# Valve.net
KiCad netlist of a schematic drawn in EAGLE
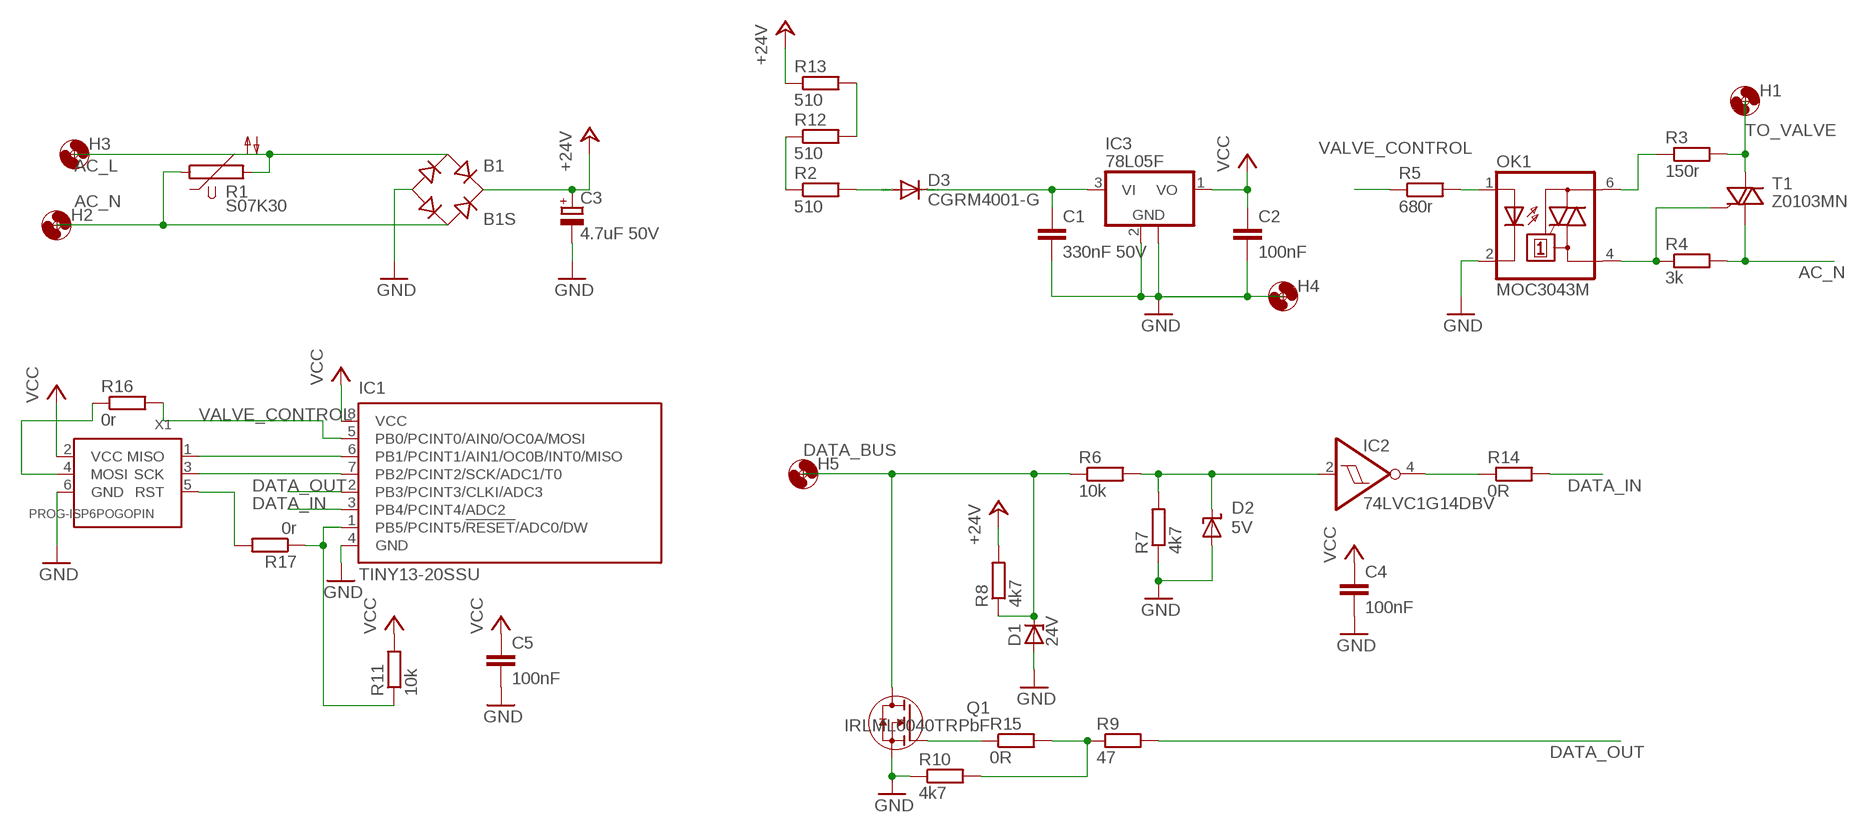
[diagram p0: schematic, sheet 1]

(export (version "E")
  (design (tool "Eeschema 10.0.6"))
  (components
    (comp (ref "B1")
      (value "B1S")
      (footprint "eagle-import:MBS")
      (libsource (lib "eagle-import") (part "BS1"))
    )
    (comp (ref "C1")
      (value "330nF 50V")
      (footprint "eagle-import:C0805K")
      (libsource (lib "eagle-import") (part "C-EUC0805K"))
    )
    (comp (ref "C2")
      (value "100nF")
      (footprint "eagle-import:C0805K")
      (libsource (lib "eagle-import") (part "C-EUC0805K"))
    )
    (comp (ref "C3")
      (value "4.7uF 50V")
      (footprint "eagle-import:D_7343-31R")
      (libsource (lib "eagle-import") (part "CPOL-EUD/7343-31R"))
    )
    (comp (ref "C4")
      (value "100nF")
      (footprint "eagle-import:0805")
      (libsource (lib "eagle-import") (part "C0805"))
    )
    (comp (ref "C5")
      (value "100nF")
      (footprint "eagle-import:C0805K")
      (libsource (lib "eagle-import") (part "C-EUC0805K"))
    )
    (comp (ref "D1")
      (value "24V")
      (footprint "eagle-import:SOT23")
      (libsource (lib "eagle-import") (part "ZENER-DIODESOT23"))
    )
    (comp (ref "D2")
      (value "5V")
      (footprint "eagle-import:SOD123")
      (libsource (lib "eagle-import") (part "ZENER"))
    )
    (comp (ref "D3")
      (value "CGRM4001-G")
      (footprint "eagle-import:SOD-123_MINI-SMA")
      (libsource (lib "eagle-import") (part "CGRM400-G1"))
    )
    (comp (ref "H1")
      (value "MOUNT-HOLE3.0")
      (footprint "eagle-import:3,0")
      (libsource (lib "eagle-import") (part "MOUNT-HOLE3.0"))
    )
    (comp (ref "H2")
      (value "MOUNT-HOLE3.0")
      (footprint "eagle-import:3,0")
      (libsource (lib "eagle-import") (part "MOUNT-HOLE3.0"))
    )
    (comp (ref "H3")
      (value "MOUNT-HOLE3.0")
      (footprint "eagle-import:3,0")
      (libsource (lib "eagle-import") (part "MOUNT-HOLE3.0"))
    )
    (comp (ref "H4")
      (value "MOUNT-HOLE3.0")
      (footprint "eagle-import:3,0")
      (libsource (lib "eagle-import") (part "MOUNT-HOLE3.0"))
    )
    (comp (ref "H5")
      (value "MOUNT-HOLE3.0")
      (footprint "eagle-import:3,0")
      (libsource (lib "eagle-import") (part "MOUNT-HOLE3.0"))
    )
    (comp (ref "IC1")
      (value "TINY13-20SSU")
      (footprint "eagle-import:8S1")
      (fields (field (name "MPN") "ATTINY13-20SSU"))
      (libsource (lib "eagle-import") (part "TINY13SSU-20"))
    )
    (comp (ref "IC2")
      (value "74LVC1G14DBV")
      (footprint "eagle-import:SOT23-5")
      (libsource (lib "eagle-import") (part "741G14DBVLVC"))
    )
    (comp (ref "IC3")
      (value "78L05F")
      (footprint "eagle-import:SOT89")
      (libsource (lib "eagle-import") (part "78LF05"))
    )
    (comp (ref "OK1")
      (value "MOC3043M")
      (footprint "eagle-import:DIL06")
      (fields (field (name "MF") "FAIRCHILD SEMICONDUCTOR") (field (name "MPN") "MOC3043-M"))
      (libsource (lib "eagle-import") (part "MOC3043M"))
    )
    (comp (ref "Q1")
      (value "IRLML0040TRPbF")
      (footprint "eagle-import:SOT-23-GSD")
      (libsource (lib "eagle-import") (part "SI2302"))
    )
    (comp (ref "R1")
      (value "S07K30")
      (footprint "eagle-import:S07K40")
      (libsource (lib "eagle-import") (part "S07K40"))
    )
    (comp (ref "R2")
      (value "510")
      (footprint "eagle-import:R2512")
      (libsource (lib "eagle-import") (part "R-EU_R2512"))
    )
    (comp (ref "R3")
      (value "150r")
      (footprint "eagle-import:R0805")
      (libsource (lib "eagle-import") (part "R-EU_R0805"))
    )
    (comp (ref "R4")
      (value "3k")
      (footprint "eagle-import:R0805")
      (libsource (lib "eagle-import") (part "R-EU_R0805"))
    )
    (comp (ref "R5")
      (value "680r")
      (footprint "eagle-import:R0805")
      (libsource (lib "eagle-import") (part "R-EU_R0805"))
    )
    (comp (ref "R6")
      (value "10k")
      (footprint "eagle-import:R0805")
      (libsource (lib "eagle-import") (part "R-EU_R0805"))
    )
    (comp (ref "R7")
      (value "4k7")
      (footprint "eagle-import:R0805")
      (libsource (lib "eagle-import") (part "R-EU_R0805"))
    )
    (comp (ref "R8")
      (value "4k7")
      (footprint "eagle-import:R0805")
      (libsource (lib "eagle-import") (part "R-EU_R0805"))
    )
    (comp (ref "R9")
      (value "47")
      (footprint "eagle-import:R0805")
      (libsource (lib "eagle-import") (part "R-EU_R0805"))
    )
    (comp (ref "R10")
      (value "4k7")
      (footprint "eagle-import:R0805")
      (libsource (lib "eagle-import") (part "R-EU_R0805"))
    )
    (comp (ref "R11")
      (value "10k")
      (footprint "eagle-import:R0805")
      (libsource (lib "eagle-import") (part "R-EU_R0805"))
    )
    (comp (ref "R12")
      (value "510")
      (footprint "eagle-import:R2512")
      (libsource (lib "eagle-import") (part "R-EU_R2512"))
    )
    (comp (ref "R13")
      (value "510")
      (footprint "eagle-import:R2512")
      (libsource (lib "eagle-import") (part "R-EU_R2512"))
    )
    (comp (ref "R14")
      (value "0R")
      (footprint "eagle-import:R1206W")
      (libsource (lib "eagle-import") (part "R-EU_R1206W"))
    )
    (comp (ref "R15")
      (value "0R")
      (footprint "eagle-import:R1206W")
      (libsource (lib "eagle-import") (part "R-EU_R1206W"))
    )
    (comp (ref "R16")
      (value "0r")
      (footprint "eagle-import:0805R")
      (libsource (lib "eagle-import") (part "R0805"))
    )
    (comp (ref "R17")
      (value "0r")
      (footprint "eagle-import:0805R")
      (libsource (lib "eagle-import") (part "R0805"))
    )
    (comp (ref "T1")
      (value "Z0103MN")
      (footprint "eagle-import:SOT223")
      (libsource (lib "eagle-import") (part "Z0103MN"))
    )
    (comp (ref "X1")
      (value "PROG-ISP6POGOPIN")
      (footprint "eagle-import:PROG_POGOPIN")
      (libsource (lib "eagle-import") (part "PROG-ISP6POGOPIN"))
    )
  )
  (nets
    (net (code "1") (name "+24V") (class "Default")
      (node (ref "B1") (pin "+") (pinfunction "+_+") (pintype "passive"))
      (node (ref "C3") (pin "+") (pinfunction "+_+") (pintype "passive"))
      (node (ref "R13") (pin "1") (pinfunction "1_1") (pintype "passive"))
      (node (ref "R8") (pin "2") (pinfunction "2_2") (pintype "passive"))
    )
    (net (code "2") (name "/AC_L") (class "Default")
      (node (ref "B1") (pin "AC1") (pinfunction "AC1_AC1") (pintype "passive"))
      (node (ref "H3") (pin "P$1") (pinfunction "P$1_P$1") (pintype "bidirectional"))
      (node (ref "R1") (pin "2") (pinfunction "2_2") (pintype "passive"))
    )
    (net (code "3") (name "/AC_N") (class "Default")
      (node (ref "B1") (pin "AC2") (pinfunction "AC2_AC2") (pintype "passive"))
      (node (ref "H2") (pin "P$1") (pinfunction "P$1_P$1") (pintype "bidirectional"))
      (node (ref "R1") (pin "1") (pinfunction "1_1") (pintype "passive"))
      (node (ref "R4") (pin "2") (pinfunction "2_2") (pintype "passive"))
      (node (ref "T1") (pin "1") (pinfunction "A1_1") (pintype "passive"))
    )
    (net (code "4") (name "/DATA_BUS") (class "Default")
      (node (ref "D1") (pin "3") (pinfunction "C_3") (pintype "passive"))
      (node (ref "H5") (pin "P$1") (pinfunction "P$1_P$1") (pintype "bidirectional"))
      (node (ref "Q1") (pin "D") (pinfunction "D_D") (pintype "passive"))
      (node (ref "R6") (pin "1") (pinfunction "1_1") (pintype "passive"))
      (node (ref "R8") (pin "1") (pinfunction "1_1") (pintype "passive"))
    )
    (net (code "5") (name "/DATA_IN") (class "Default")
      (node (ref "IC1") (pin "3") (pinfunction "PB4/PCINT4/ADC2_3") (pintype "bidirectional"))
      (node (ref "R14") (pin "2") (pinfunction "2_2") (pintype "passive"))
    )
    (net (code "6") (name "/DATA_OUT") (class "Default")
      (node (ref "IC1") (pin "2") (pinfunction "PB3/PCINT3/CLKI/ADC3_2") (pintype "bidirectional"))
      (node (ref "R9") (pin "2") (pinfunction "2_2") (pintype "passive"))
    )
    (net (code "7") (name "/TO_VALVE") (class "Default")
      (node (ref "H1") (pin "P$1") (pinfunction "P$1_P$1") (pintype "bidirectional"))
      (node (ref "R3") (pin "2") (pinfunction "2_2") (pintype "passive"))
      (node (ref "T1") (pin "2") (pinfunction "A2_2") (pintype "passive"))
      (node (ref "T1") (pin "4") (pinfunction "A2_4") (pintype "passive"))
    )
    (net (code "8") (name "/VALVE_CONTROL") (class "Default")
      (node (ref "IC1") (pin "5") (pinfunction "PB0/PCINT0/AIN0/OC0A/MOSI_5") (pintype "bidirectional"))
      (node (ref "R16") (pin "2") (pinfunction "2_2") (pintype "passive"))
      (node (ref "R5") (pin "1") (pinfunction "1_1") (pintype "passive"))
    )
    (net (code "9") (name "GND") (class "Default")
      (node (ref "B1") (pin "-") (pinfunction "-_-") (pintype "passive"))
      (node (ref "C1") (pin "2") (pinfunction "2_2") (pintype "passive"))
      (node (ref "C2") (pin "2") (pinfunction "2_2") (pintype "passive"))
      (node (ref "C3") (pin "-") (pinfunction "-_-") (pintype "passive"))
      (node (ref "C4") (pin "2") (pinfunction "2_2") (pintype "passive"))
      (node (ref "C5") (pin "2") (pinfunction "2_2") (pintype "passive"))
      (node (ref "D1") (pin "1") (pinfunction "A_1") (pintype "passive"))
      (node (ref "D2") (pin "A") (pinfunction "A_A") (pintype "passive"))
      (node (ref "H4") (pin "P$1") (pinfunction "P$1_P$1") (pintype "bidirectional"))
      (node (ref "IC1") (pin "4") (pinfunction "GND_4") (pintype "power_in"))
      (node (ref "IC3") (pin "2") (pinfunction "GND_2") (pintype "passive"))
      (node (ref "IC3") (pin "2@1") (pinfunction "GND_2@1") (pintype "passive"))
      (node (ref "OK1") (pin "2") (pinfunction "C_2") (pintype "passive"))
      (node (ref "Q1") (pin "S") (pinfunction "S_S") (pintype "passive"))
      (node (ref "R10") (pin "1") (pinfunction "1_1") (pintype "passive"))
      (node (ref "R7") (pin "1") (pinfunction "1_1") (pintype "passive"))
      (node (ref "X1") (pin "6") (pinfunction "GND_6") (pintype "power_in"))
    )
    (net (code "10") (name "Net-(D3-PadA)") (class "Default")
      (node (ref "D3") (pin "A") (pinfunction "A_A") (pintype "passive"))
      (node (ref "R2") (pin "2") (pinfunction "2_2") (pintype "passive"))
    )
    (net (code "11") (name "Net-(IC1-PB1{slash}PCINT1{slash}AIN1{slash}OC0B{slash}INT0{slash}MISO)") (class "Default")
      (node (ref "IC1") (pin "6") (pinfunction "PB1/PCINT1/AIN1/OC0B/INT0/MISO_6") (pintype "bidirectional"))
      (node (ref "X1") (pin "1") (pinfunction "MISO_1") (pintype "bidirectional"))
    )
    (net (code "12") (name "Net-(IC1-PB2{slash}PCINT2{slash}SCK{slash}ADC1{slash}T0)") (class "Default")
      (node (ref "IC1") (pin "7") (pinfunction "PB2/PCINT2/SCK/ADC1/T0_7") (pintype "bidirectional"))
      (node (ref "X1") (pin "3") (pinfunction "SCK_3") (pintype "bidirectional"))
    )
    (net (code "13") (name "Net-(IC1-PB5{slash}PCINT5{slash}~{RESET}{slash}ADC0{slash}DW)") (class "Default")
      (node (ref "IC1") (pin "1") (pinfunction "PB5/PCINT5/~{RESET}/ADC0/DW_1") (pintype "bidirectional"))
      (node (ref "R11") (pin "1") (pinfunction "1_1") (pintype "passive"))
      (node (ref "R17") (pin "1") (pinfunction "1_1") (pintype "passive"))
    )
    (net (code "14") (name "Net-(IC2A-I)") (class "Default")
      (node (ref "D2") (pin "C") (pinfunction "C_C") (pintype "passive"))
      (node (ref "IC2") (pin "2") (pinfunction "I_2") (pintype "input"))
      (node (ref "R6") (pin "2") (pinfunction "2_2") (pintype "passive"))
      (node (ref "R7") (pin "2") (pinfunction "2_2") (pintype "passive"))
    )
    (net (code "15") (name "Net-(IC2A-O)") (class "Default")
      (node (ref "IC2") (pin "4") (pinfunction "O_4") (pintype "output"))
      (node (ref "R14") (pin "1") (pinfunction "1_1") (pintype "passive"))
    )
    (net (code "16") (name "Net-(IC3-VI)") (class "Default")
      (node (ref "C1") (pin "1") (pinfunction "1_1") (pintype "passive"))
      (node (ref "D3") (pin "C") (pinfunction "C_C") (pintype "passive"))
      (node (ref "IC3") (pin "3") (pinfunction "VI_3") (pintype "input"))
    )
    (net (code "17") (name "Net-(OK1-A)") (class "Default")
      (node (ref "OK1") (pin "1") (pinfunction "A_1") (pintype "passive"))
      (node (ref "R5") (pin "2") (pinfunction "2_2") (pintype "passive"))
    )
    (net (code "18") (name "Net-(OK1-A1)") (class "Default")
      (node (ref "OK1") (pin "4") (pinfunction "A1_4") (pintype "passive"))
      (node (ref "R4") (pin "1") (pinfunction "1_1") (pintype "passive"))
      (node (ref "T1") (pin "3") (pinfunction "G_3") (pintype "passive"))
    )
    (net (code "19") (name "Net-(OK1-A2)") (class "Default")
      (node (ref "OK1") (pin "6") (pinfunction "A2_6") (pintype "passive"))
      (node (ref "R3") (pin "1") (pinfunction "1_1") (pintype "passive"))
    )
    (net (code "20") (name "Net-(Q1-PadG)") (class "Default")
      (node (ref "Q1") (pin "G") (pinfunction "G_G") (pintype "passive"))
      (node (ref "R15") (pin "1") (pinfunction "1_1") (pintype "passive"))
    )
    (net (code "21") (name "Net-(R10-Pad2)") (class "Default")
      (node (ref "R10") (pin "2") (pinfunction "2_2") (pintype "passive"))
      (node (ref "R15") (pin "2") (pinfunction "2_2") (pintype "passive"))
      (node (ref "R9") (pin "1") (pinfunction "1_1") (pintype "passive"))
    )
    (net (code "22") (name "Net-(R12-Pad1)") (class "Default")
      (node (ref "R12") (pin "1") (pinfunction "1_1") (pintype "passive"))
      (node (ref "R2") (pin "1") (pinfunction "1_1") (pintype "passive"))
    )
    (net (code "23") (name "Net-(R12-Pad2)") (class "Default")
      (node (ref "R12") (pin "2") (pinfunction "2_2") (pintype "passive"))
      (node (ref "R13") (pin "2") (pinfunction "2_2") (pintype "passive"))
    )
    (net (code "24") (name "Net-(X1-MOSI)") (class "Default")
      (node (ref "R16") (pin "1") (pinfunction "1_1") (pintype "passive"))
      (node (ref "X1") (pin "4") (pinfunction "MOSI_4") (pintype "bidirectional"))
    )
    (net (code "25") (name "Net-(X1-RST)") (class "Default")
      (node (ref "R17") (pin "2") (pinfunction "2_2") (pintype "passive"))
      (node (ref "X1") (pin "5") (pinfunction "RST_5") (pintype "bidirectional"))
    )
    (net (code "26") (name "VCC") (class "Default")
      (node (ref "C2") (pin "1") (pinfunction "1_1") (pintype "passive"))
      (node (ref "C4") (pin "1") (pinfunction "1_1") (pintype "passive"))
      (node (ref "C5") (pin "1") (pinfunction "1_1") (pintype "passive"))
      (node (ref "IC1") (pin "8") (pinfunction "VCC_8") (pintype "power_in"))
      (node (ref "IC3") (pin "1") (pinfunction "VO_1") (pintype "passive"))
      (node (ref "R11") (pin "2") (pinfunction "2_2") (pintype "passive"))
      (node (ref "X1") (pin "2") (pinfunction "VCC_2") (pintype "bidirectional"))
    )
  )
)
